# P2.net
KiCad netlist of a schematic drawn in Altium Designer
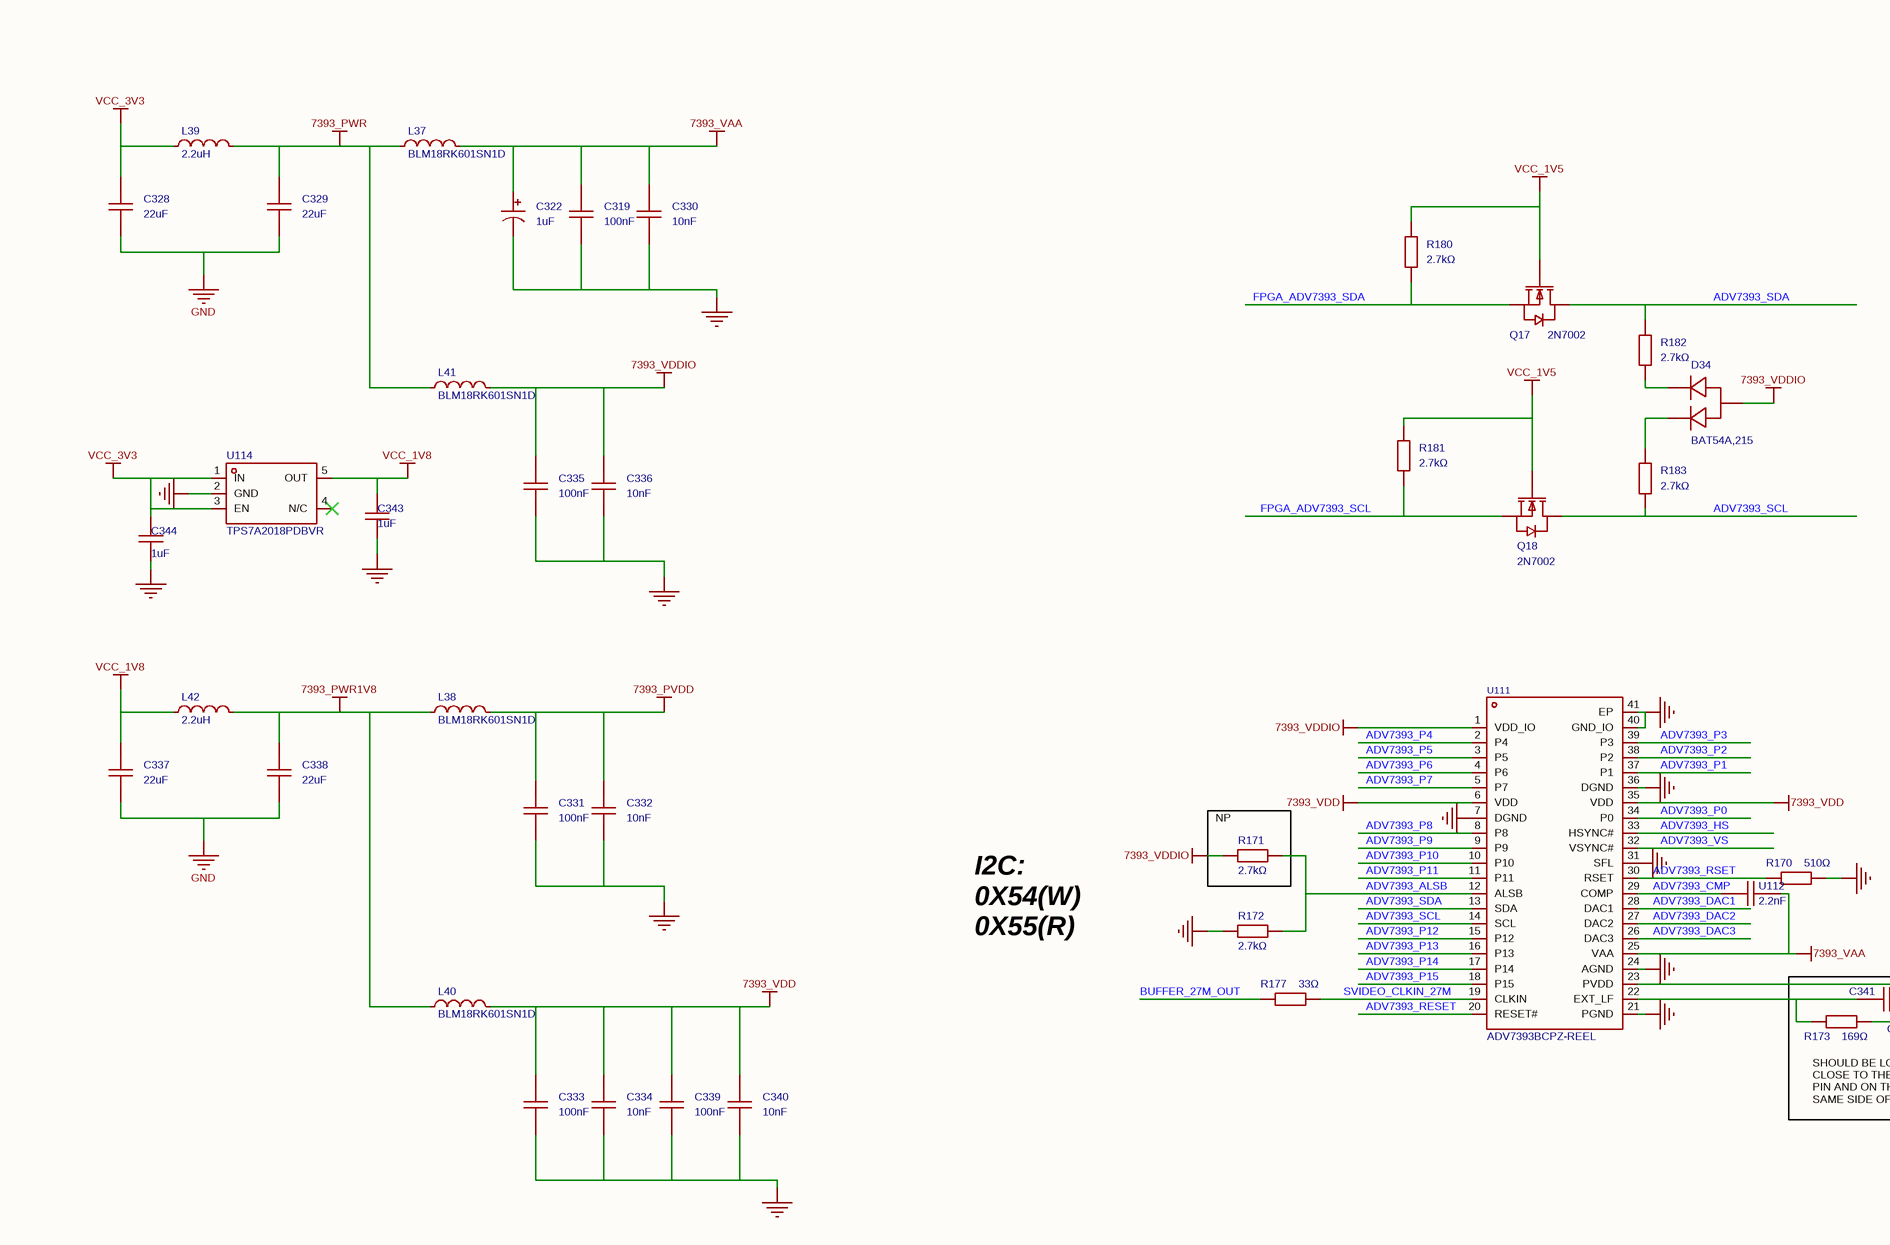
[diagram p0: P2.schdoc, top left]
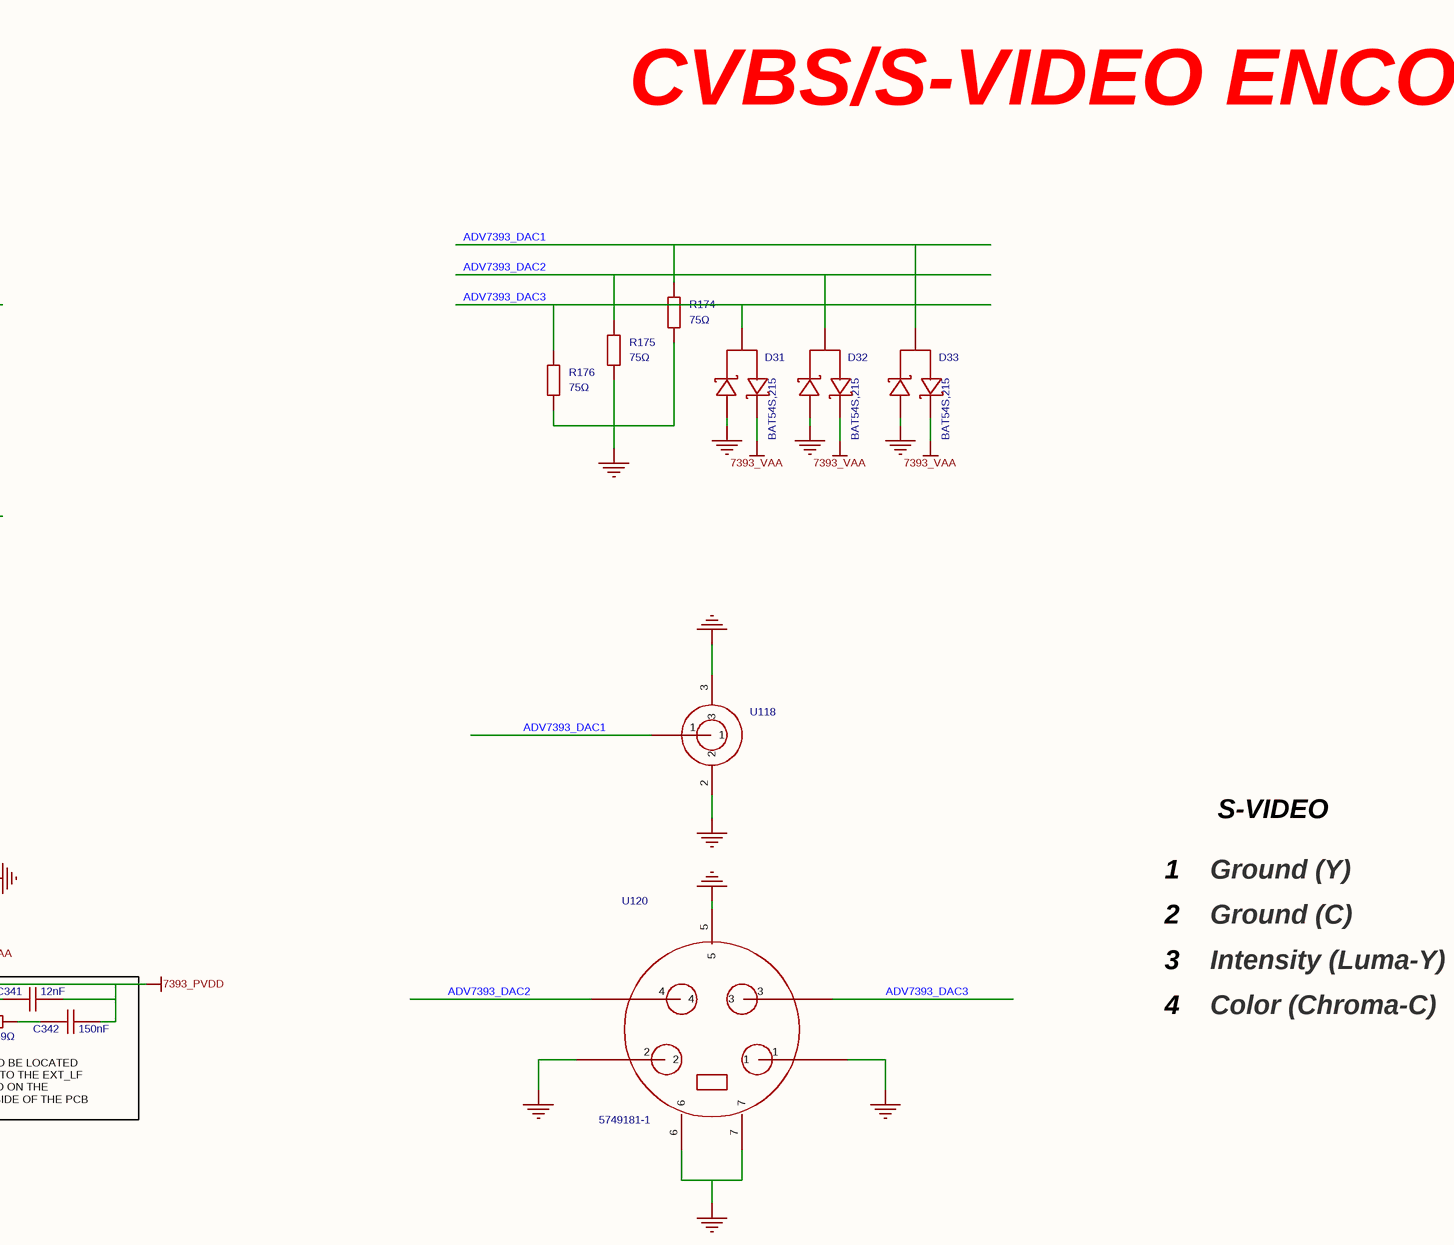
[diagram p1: P2.schdoc, top right]
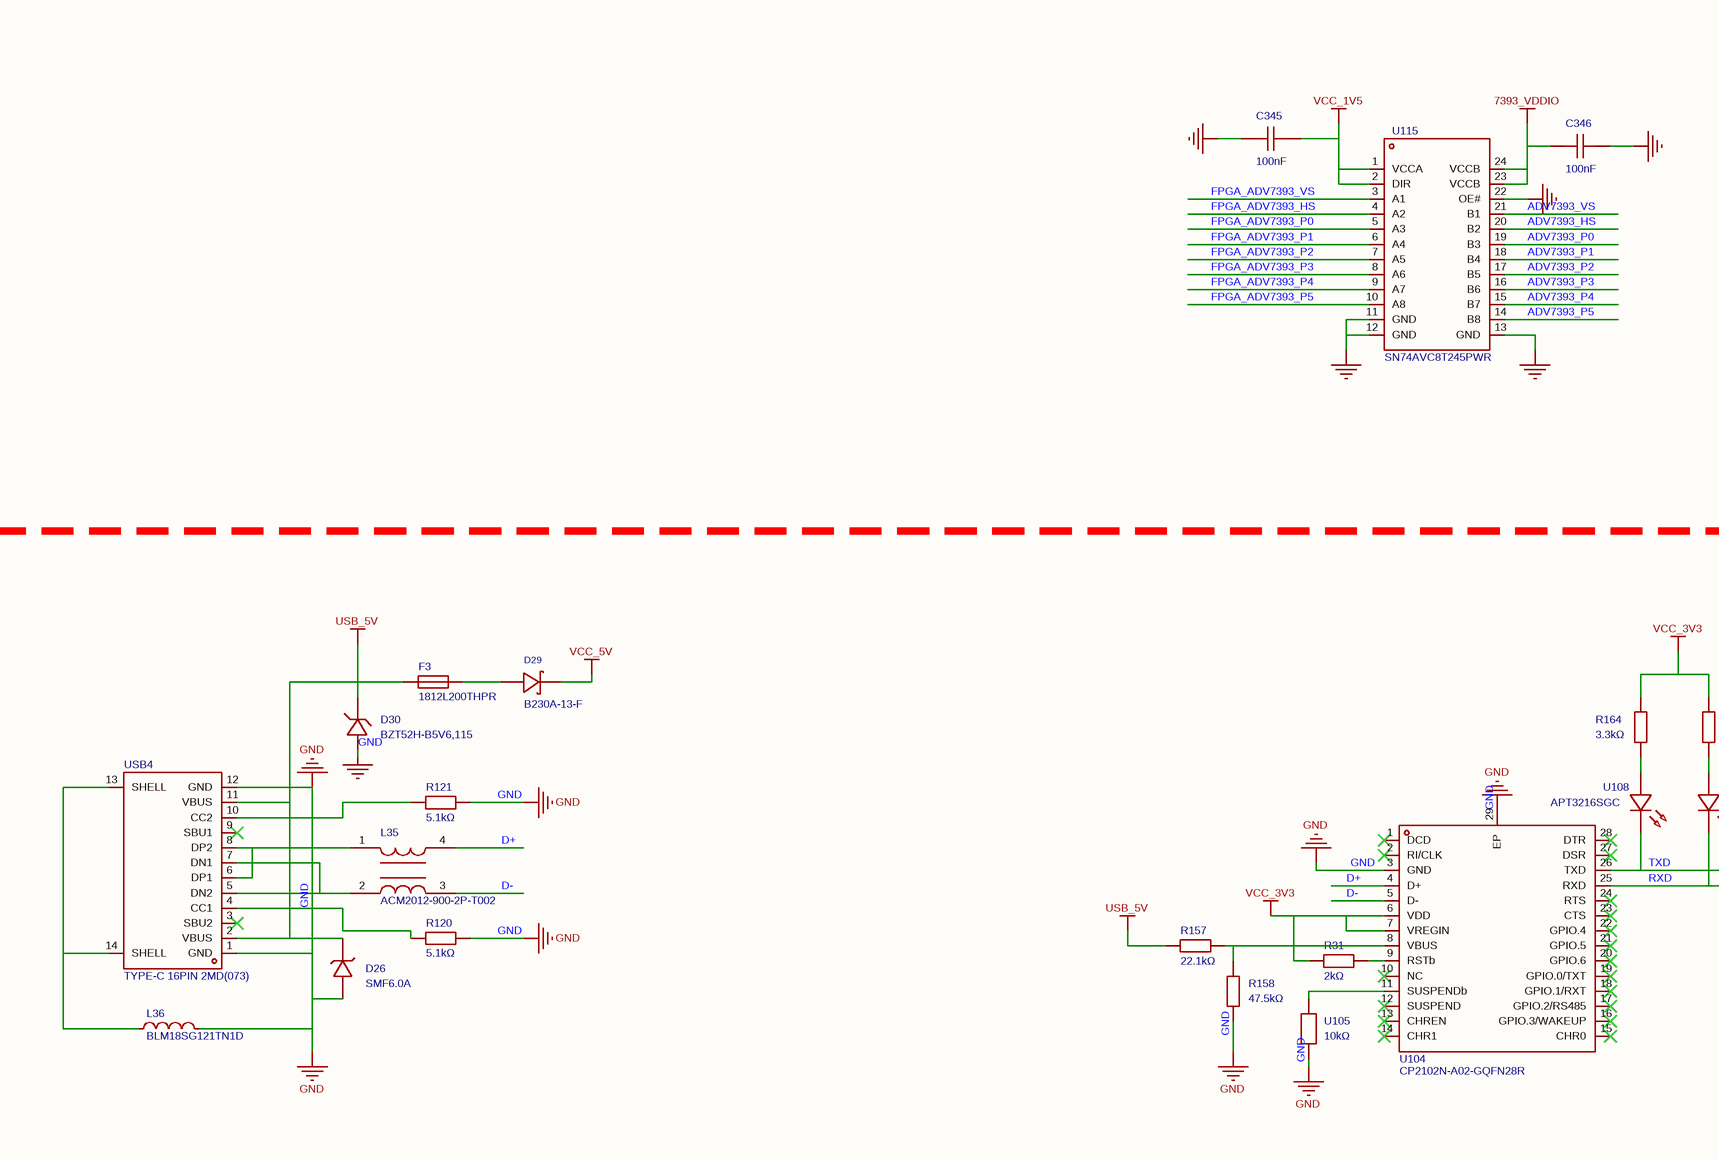
[diagram p2: P2.schdoc, bottom left]
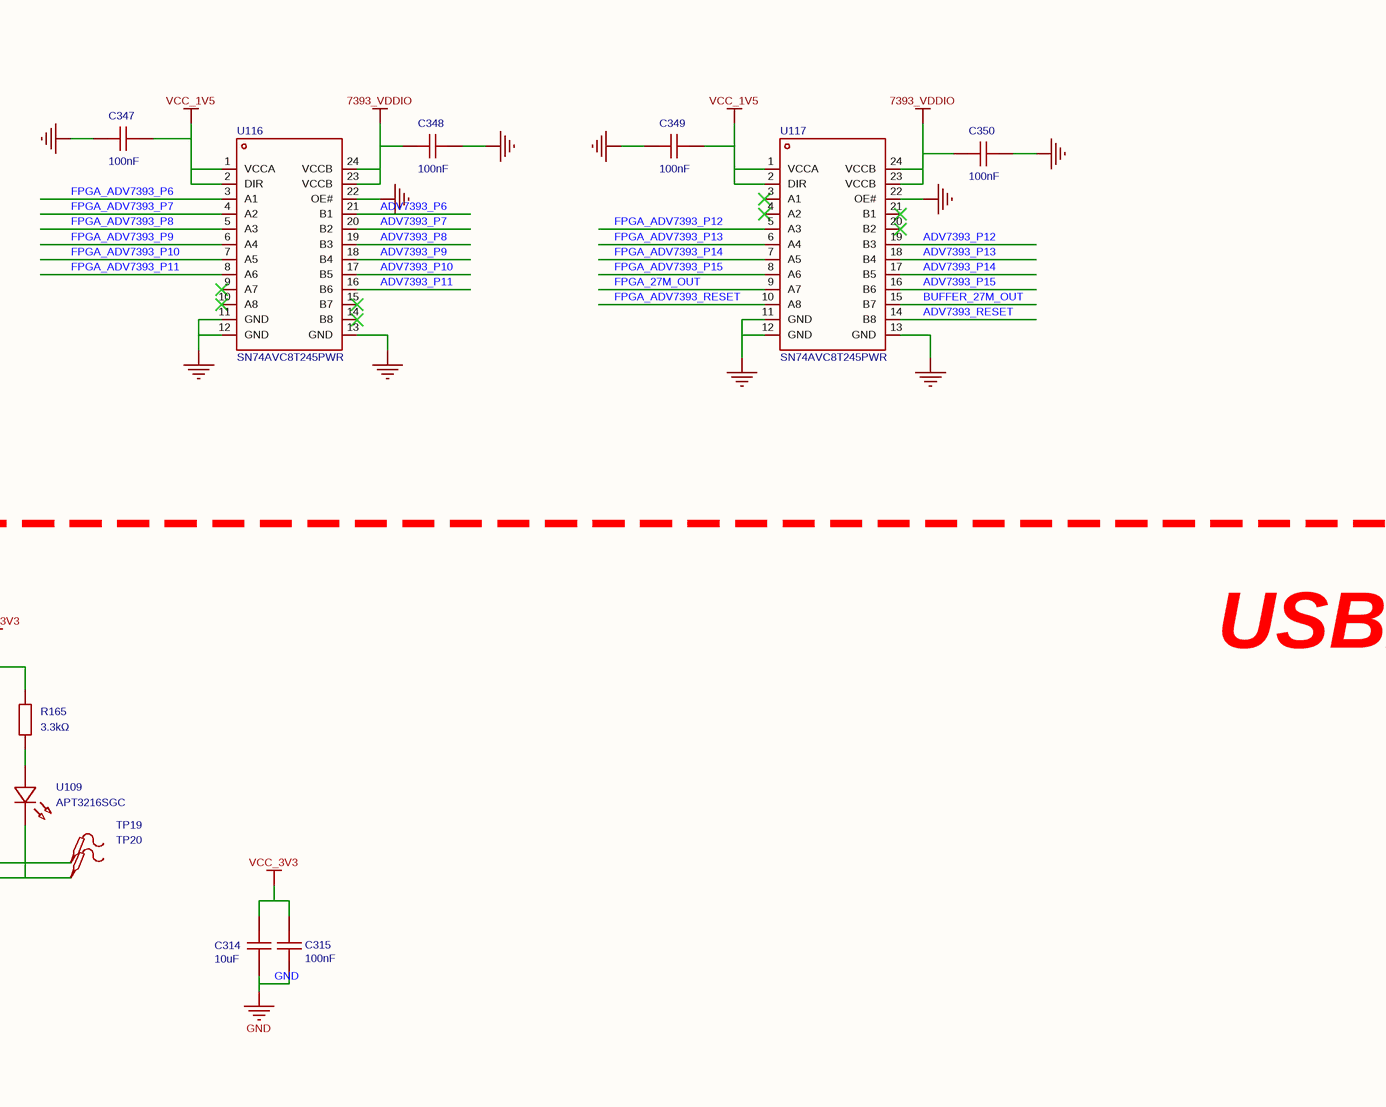
[diagram p3: P2.schdoc, bottom right]

(export (version "E")
  (design (tool "Eeschema 10.0.6"))
  (components
    (comp (ref "C314")
      (value "10uF")
      (footprint "C0603")
      (fields (field (name "MANUFACTURER") "TDK") (field (name "MANUFACTURER PART") "C1608X5R1A106M080AC"))
      (libsource (lib "altium-import") (part "root_1_10uF_"))
    )
    (comp (ref "C315")
      (value "100nF")
      (footprint "C0603")
      (description "容值:100nF;精度:±10%;额定电压:50V;材质(温度系数):X7R;")
      (fields
        (field (name "MANUFACTURER") "muRata(村田)")
        (field (name "MANUFACTURER PART") "GRM188R71H104KA93D")
      )
      (libsource (lib "altium-import") (part "root_1_GRM188R71H104KA93D_"))
    )
    (comp (ref "C319")
      (value "100nF")
      (footprint "C0402")
      (description "容值:100nF;精度:±10%;额定电压:10V;材质(温度系数):X7R;")
      (fields
        (field (name "MANUFACTURER") "muRata(村田)")
        (field (name "MANUFACTURERPART") "GCM155R71A104KA55D")
      )
      (libsource (lib "altium-import") (part "root_2_GCM155R71A104KA55D_"))
    )
    (comp (ref "C322")
      (value "1uF")
      (footprint "CAP-SMD_L3.2-W1.6-FD-1")
      (description "容值:1uF;精度:±10%;额定电压:35V;等效串联电阻:7.5Ω;")
      (fields
        (field (name "MANUFACTURER") "VISHAY(威世)")
        (field (name "MANUFACTURER PART") "293D105X9035A2TE3")
      )
      (libsource (lib "altium-import") (part "root_1_293D105X9035A2TE3_"))
    )
    (comp (ref "C328")
      (value "22uF")
      (footprint "C1210")
      (description "容值:22uF;精度:±10%;额定电压:25V;材质(温度系数):X7R;")
      (fields
        (field (name "MANUFACTURER") "muRata(村田)")
        (field (name "MANUFACTURER PART") "GRM32ER71E226KE15L")
      )
      (libsource (lib "altium-import") (part "root_1_GRM32ER71E226KE15L_"))
    )
    (comp (ref "C329")
      (value "22uF")
      (footprint "C1210")
      (description "容值:22uF;精度:±10%;额定电压:25V;材质(温度系数):X7R;")
      (fields
        (field (name "MANUFACTURER") "muRata(村田)")
        (field (name "MANUFACTURER PART") "GRM32ER71E226KE15L")
      )
      (libsource (lib "altium-import") (part "root_1_GRM32ER71E226KE15L_"))
    )
    (comp (ref "C330")
      (value "10nF")
      (footprint "C0402")
      (description "容值:10nF;精度:±10%;额定电压:50V;材质(温度系数):X7R;")
      (fields
        (field (name "MANUFACTURER") "muRata(村田)")
        (field (name "MANUFACTURER PART") "GRM155R71H103KA88D")
      )
      (libsource (lib "altium-import") (part "root_1_GRM155R71H103KA88D_"))
    )
    (comp (ref "C331")
      (value "100nF")
      (footprint "C0402")
      (description "容值:100nF;精度:±10%;额定电压:10V;材质(温度系数):X7R;")
      (fields
        (field (name "MANUFACTURER") "muRata(村田)")
        (field (name "MANUFACTURERPART") "GCM155R71A104KA55D")
      )
      (libsource (lib "altium-import") (part "root_2_GCM155R71A104KA55D_"))
    )
    (comp (ref "C332")
      (value "10nF")
      (footprint "C0402")
      (description "容值:10nF;精度:±10%;额定电压:50V;材质(温度系数):X7R;")
      (fields
        (field (name "MANUFACTURER") "muRata(村田)")
        (field (name "MANUFACTURER PART") "GRM155R71H103KA88D")
      )
      (libsource (lib "altium-import") (part "root_1_GRM155R71H103KA88D_"))
    )
    (comp (ref "C333")
      (value "100nF")
      (footprint "C0402")
      (description "容值:100nF;精度:±10%;额定电压:10V;材质(温度系数):X7R;")
      (fields
        (field (name "MANUFACTURER") "muRata(村田)")
        (field (name "MANUFACTURERPART") "GCM155R71A104KA55D")
      )
      (libsource (lib "altium-import") (part "root_2_GCM155R71A104KA55D_"))
    )
    (comp (ref "C334")
      (value "10nF")
      (footprint "C0402")
      (description "容值:10nF;精度:±10%;额定电压:50V;材质(温度系数):X7R;")
      (fields
        (field (name "MANUFACTURER") "muRata(村田)")
        (field (name "MANUFACTURER PART") "GRM155R71H103KA88D")
      )
      (libsource (lib "altium-import") (part "root_1_GRM155R71H103KA88D_"))
    )
    (comp (ref "C335")
      (value "100nF")
      (footprint "C0402")
      (description "容值:100nF;精度:±10%;额定电压:10V;材质(温度系数):X7R;")
      (fields
        (field (name "MANUFACTURER") "muRata(村田)")
        (field (name "MANUFACTURERPART") "GCM155R71A104KA55D")
      )
      (libsource (lib "altium-import") (part "root_2_GCM155R71A104KA55D_"))
    )
    (comp (ref "C336")
      (value "10nF")
      (footprint "C0402")
      (description "容值:10nF;精度:±10%;额定电压:50V;材质(温度系数):X7R;")
      (fields
        (field (name "MANUFACTURER") "muRata(村田)")
        (field (name "MANUFACTURER PART") "GRM155R71H103KA88D")
      )
      (libsource (lib "altium-import") (part "root_1_GRM155R71H103KA88D_"))
    )
    (comp (ref "C337")
      (value "22uF")
      (footprint "C1210")
      (description "容值:22uF;精度:±10%;额定电压:25V;材质(温度系数):X7R;")
      (fields
        (field (name "MANUFACTURER") "muRata(村田)")
        (field (name "MANUFACTURER PART") "GRM32ER71E226KE15L")
      )
      (libsource (lib "altium-import") (part "root_1_GRM32ER71E226KE15L_"))
    )
    (comp (ref "C338")
      (value "22uF")
      (footprint "C1210")
      (description "容值:22uF;精度:±10%;额定电压:25V;材质(温度系数):X7R;")
      (fields
        (field (name "MANUFACTURER") "muRata(村田)")
        (field (name "MANUFACTURER PART") "GRM32ER71E226KE15L")
      )
      (libsource (lib "altium-import") (part "root_1_GRM32ER71E226KE15L_"))
    )
    (comp (ref "C339")
      (value "100nF")
      (footprint "C0402")
      (description "容值:100nF;精度:±10%;额定电压:10V;材质(温度系数):X7R;")
      (fields
        (field (name "MANUFACTURER") "muRata(村田)")
        (field (name "MANUFACTURERPART") "GCM155R71A104KA55D")
      )
      (libsource (lib "altium-import") (part "root_2_GCM155R71A104KA55D_"))
    )
    (comp (ref "C340")
      (value "10nF")
      (footprint "C0402")
      (description "容值:10nF;精度:±10%;额定电压:50V;材质(温度系数):X7R;")
      (fields
        (field (name "MANUFACTURER") "muRata(村田)")
        (field (name "MANUFACTURER PART") "GRM155R71H103KA88D")
      )
      (libsource (lib "altium-import") (part "root_1_GRM155R71H103KA88D_"))
    )
    (comp (ref "C341")
      (value "12nF")
      (footprint "C0402")
      (description "容值:12nF;精度:±10%;额定电压:25V;材质(温度系数):X7R;")
      (fields
        (field (name "MANUFACTURER") "YAGEO(国巨)")
        (field (name "MANUFACTURER PART") "CC0402KRX7R8BB123")
      )
      (libsource (lib "altium-import") (part "root_0_CC0402KRX7R8BB123_"))
    )
    (comp (ref "C342")
      (value "150nF")
      (footprint "C0402")
      (description "容值:150nF;精度:±10%;额定电压:16V;材质(温度系数):X7R;")
      (fields
        (field (name "MANUFACTURER") "muRata(村田)")
        (field (name "MANUFACTURER PART") "GRM155R71C154KA12D")
      )
      (libsource (lib "altium-import") (part "root_0_GRM155R71C154KA12D_"))
    )
    (comp (ref "C343")
      (value "1uF")
      (footprint "C0402")
      (description "容值:1uF;精度:±10%;额定电压:25V;材质(温度系数):X5R;")
      (fields
        (field (name "MANUFACTURER PART") "GRM155R61E105KA12D")
        (field (name "MANUFACTURER") "muRata(村田)")
      )
      (libsource (lib "altium-import") (part "root_1_GRM155R61E105KA12D_"))
    )
    (comp (ref "C344")
      (value "1uF")
      (footprint "C0402")
      (description "容值:1uF;精度:±10%;额定电压:25V;材质(温度系数):X5R;")
      (fields
        (field (name "MANUFACTURER PART") "GRM155R61E105KA12D")
        (field (name "MANUFACTURER") "muRata(村田)")
      )
      (libsource (lib "altium-import") (part "root_1_GRM155R61E105KA12D_"))
    )
    (comp (ref "C345")
      (value "100nF")
      (footprint "C0603")
      (description "容值:100nF;精度:±10%;额定电压:50V;材质(温度系数):X7R;")
      (fields
        (field (name "MANUFACTURER") "muRata(村田)")
        (field (name "MANUFACTURER PART") "GRM188R71H104KA93D")
      )
      (libsource (lib "altium-import") (part "root_2_GRM188R71H104KA93D_"))
    )
    (comp (ref "C346")
      (value "100nF")
      (footprint "C0603")
      (description "容值:100nF;精度:±10%;额定电压:50V;材质(温度系数):X7R;")
      (fields
        (field (name "MANUFACTURER") "muRata(村田)")
        (field (name "MANUFACTURER PART") "GRM188R71H104KA93D")
      )
      (libsource (lib "altium-import") (part "root_0_GRM188R71H104KA93D_"))
    )
    (comp (ref "C347")
      (value "100nF")
      (footprint "C0603")
      (description "容值:100nF;精度:±10%;额定电压:50V;材质(温度系数):X7R;")
      (fields
        (field (name "MANUFACTURER") "muRata(村田)")
        (field (name "MANUFACTURER PART") "GRM188R71H104KA93D")
      )
      (libsource (lib "altium-import") (part "root_2_GRM188R71H104KA93D_"))
    )
    (comp (ref "C348")
      (value "100nF")
      (footprint "C0603")
      (description "容值:100nF;精度:±10%;额定电压:50V;材质(温度系数):X7R;")
      (fields
        (field (name "MANUFACTURER") "muRata(村田)")
        (field (name "MANUFACTURER PART") "GRM188R71H104KA93D")
      )
      (libsource (lib "altium-import") (part "root_0_GRM188R71H104KA93D_"))
    )
    (comp (ref "C349")
      (value "100nF")
      (footprint "C0603")
      (description "容值:100nF;精度:±10%;额定电压:50V;材质(温度系数):X7R;")
      (fields
        (field (name "MANUFACTURER") "muRata(村田)")
        (field (name "MANUFACTURER PART") "GRM188R71H104KA93D")
      )
      (libsource (lib "altium-import") (part "root_2_GRM188R71H104KA93D_"))
    )
    (comp (ref "C350")
      (value "100nF")
      (footprint "C0603")
      (description "容值:100nF;精度:±10%;额定电压:50V;材质(温度系数):X7R;")
      (fields
        (field (name "MANUFACTURER") "muRata(村田)")
        (field (name "MANUFACTURER PART") "GRM188R71H104KA93D")
      )
      (libsource (lib "altium-import") (part "root_0_GRM188R71H104KA93D_"))
    )
    (comp (ref "D26")
      (value "SMF6.0A")
      (footprint "SOD-123FL_L2.8-W1.8-LS3.7-RD-1")
      (description "极性:单向;反向截止电压(Vrwm):6V;最大钳位电压:10.3V;峰值脉冲电流(Ipp)@10/1000us:19.4A;击穿电压:6.7V;")
      (fields (field (name "MANUFACTURER") "FTR(乔光电子)"))
      (libsource (lib "altium-import") (part "root_3_SMF6.0A_C708002_"))
    )
    (comp (ref "D29")
      (value "B230A-13-F")
      (footprint "SMA_L4.4-W2.6-LS5.0-RD")
      (description "正向压降(Vf):500mV@2A;直流反向耐压(Vr):30V;平均整流电流(Io):2A;")
      (fields (field (name "MANUFACTURER") "DIODES(美台)"))
      (libsource (lib "altium-import") (part "root_0_mirrored_B230A-13-F_"))
    )
    (comp (ref "D30")
      (value "BZT52H-B5V6,115")
      (footprint "SOD-123F_L2.6-W1.6-LS3.5-RD")
      (description "二极管配置:独立式;稳压值(标称值):5.6V;稳压值(范围):5.49V~5.71V;功率:375mW;精度:±2%;")
      (fields (field (name "MANUFACTURER") "Nexperia(安世)") (field (name "TOLERANCE") "±2%"))
      (libsource (lib "altium-import") (part "root_3_mirrored_BZT52H-B5V6,115_"))
    )
    (comp (ref "D31")
      (value "BAT54S,215")
      (footprint "SOT-23-3_L3.0-W1.7-P0.95-LS2.9-BR")
      (description "二极管配置:1对串联式;正向压降(Vf):800mV@100mA;直流反向耐压(Vr):30V;平均整流电流(Io):200mA;")
      (fields (field (name "MANUFACTURER") "Nexperia(安世)"))
      (libsource (lib "altium-import") (part "root_1_BAT54S,215_"))
    )
    (comp (ref "D32")
      (value "BAT54S,215")
      (footprint "SOT-23-3_L3.0-W1.7-P0.95-LS2.9-BR")
      (description "二极管配置:1对串联式;正向压降(Vf):800mV@100mA;直流反向耐压(Vr):30V;平均整流电流(Io):200mA;")
      (fields (field (name "MANUFACTURER") "Nexperia(安世)"))
      (libsource (lib "altium-import") (part "root_1_BAT54S,215_"))
    )
    (comp (ref "D33")
      (value "BAT54S,215")
      (footprint "SOT-23-3_L3.0-W1.7-P0.95-LS2.9-BR")
      (description "二极管配置:1对串联式;正向压降(Vf):800mV@100mA;直流反向耐压(Vr):30V;平均整流电流(Io):200mA;")
      (fields (field (name "MANUFACTURER") "Nexperia(安世)"))
      (libsource (lib "altium-import") (part "root_1_BAT54S,215_"))
    )
    (comp (ref "D34")
      (value "BAT54A,215")
      (footprint "SOT-23-3_L3.0-W1.7-P0.95-LS2.9-BR")
      (description "二极管配置:1对共阳极;直流反向耐压(Vr):30V;平均整流电流(Io):200mA;")
      (fields (field (name "MANUFACTURER") "Nexperia(安世)"))
      (libsource (lib "altium-import") (part "root_3_BAT54A,215_"))
    )
    (comp (ref "F3")
      (value "1812L200THPR")
      (footprint "F1812")
      (description "最大电压:8V;最大电流:100A;保持电流:2A;跳闸电流:3.5A;")
      (fields (field (name "MANUFACTURER") "Littelfuse(美国力特)"))
      (libsource (lib "altium-import") (part "root_0_mirrored_1812L200THPR_"))
    )
    (comp (ref "L35")
      (value "ACM2012-900-2P-T002")
      (footprint "IND-SMD_4P-L2.0-W1.2-TL")
      (description "线路数:2;阻抗 @ 频率:90Ω@100MHz;额定电流:400mA;直流电阻(DCR):190mΩ;直流额定电压(VDC):50V;工作温度:-25℃~+85℃;耐电压:50V;")
      (fields (field (name "MANUFACTURER") "TDK"))
      (libsource (lib "altium-import") (part "root_0_ACM2012-900-2P-T002_"))
    )
    (comp (ref "L36")
      (value "BLM18SG121TN1D")
      (footprint "L0603")
      (description "标称阻抗@测试频率:120Ω@100MHz;误差:±25%;直流电阻(RDC):25mΩ;")
      (fields (field (name "MANUFACTURER") "muRata(村田)") (field (name "TOLERANCE") "±25%"))
      (libsource (lib "altium-import") (part "root_0_BLM18SG121TN1D_"))
    )
    (comp (ref "L37")
      (value "BLM18RK601SN1D")
      (footprint "L0603")
      (description "标称阻抗@测试频率:600Ω@100MHz;误差:±25%;直流电阻(RDC):600mΩ;")
      (fields (field (name "MANUFACTURER") "muRata(村田)") (field (name "TOLERANCE") "±25%"))
      (libsource (lib "altium-import") (part "root_0_BLM18RK601SN1D_"))
    )
    (comp (ref "L38")
      (value "BLM18RK601SN1D")
      (footprint "L0603")
      (description "标称阻抗@测试频率:600Ω@100MHz;误差:±25%;直流电阻(RDC):600mΩ;")
      (fields (field (name "MANUFACTURER") "muRata(村田)") (field (name "TOLERANCE") "±25%"))
      (libsource (lib "altium-import") (part "root_0_BLM18RK601SN1D_"))
    )
    (comp (ref "L39")
      (value "2.2uH")
      (footprint "IND-SMD_L7.0-W6.6")
      (description "电感值:2.2uH;精度:±20%;额定电流:9.5A;饱和电流(Isat):10A;类型:一体成型电感;")
      (fields (field (name "MANUFACTURER") "cjiang(长江微电)") (field (name "MANUFACTURERPART") "FXL0630-2R2-M"))
      (libsource (lib "altium-import") (part "root_0_FXL0630-2R2-M_"))
    )
    (comp (ref "L40")
      (value "BLM18RK601SN1D")
      (footprint "L0603")
      (description "标称阻抗@测试频率:600Ω@100MHz;误差:±25%;直流电阻(RDC):600mΩ;")
      (fields (field (name "MANUFACTURER") "muRata(村田)") (field (name "TOLERANCE") "±25%"))
      (libsource (lib "altium-import") (part "root_0_BLM18RK601SN1D_"))
    )
    (comp (ref "L41")
      (value "BLM18RK601SN1D")
      (footprint "L0603")
      (description "标称阻抗@测试频率:600Ω@100MHz;误差:±25%;直流电阻(RDC):600mΩ;")
      (fields (field (name "MANUFACTURER") "muRata(村田)") (field (name "TOLERANCE") "±25%"))
      (libsource (lib "altium-import") (part "root_0_BLM18RK601SN1D_"))
    )
    (comp (ref "L42")
      (value "2.2uH")
      (footprint "IND-SMD_L7.0-W6.6")
      (description "电感值:2.2uH;精度:±20%;额定电流:9.5A;饱和电流(Isat):10A;类型:一体成型电感;")
      (fields (field (name "MANUFACTURER") "cjiang(长江微电)") (field (name "MANUFACTURERPART") "FXL0630-2R2-M"))
      (libsource (lib "altium-import") (part "root_0_FXL0630-2R2-M_"))
    )
    (comp (ref "Q17")
      (value "2N7002")
      (footprint "SOT-23-3_L2.9-W1.3-P1.90-LS2.4-BR")
      (fields (field (name "MANUFACTURER") "CJ(江苏长电/长晶)"))
      (libsource (lib "altium-import") (part "root_3_2N7002_C8545_"))
    )
    (comp (ref "Q18")
      (value "2N7002")
      (footprint "SOT-23-3_L2.9-W1.3-P1.90-LS2.4-BR")
      (fields (field (name "MANUFACTURER") "CJ(江苏长电/长晶)"))
      (libsource (lib "altium-import") (part "root_3_2N7002_C8545_"))
    )
    (comp (ref "R31")
      (value "2kΩ")
      (footprint "R0402")
      (description "电阻类型:厚膜电阻;阻值:2kΩ;精度:±1%;功率:62.5mW;最大工作电压:50V;温度系数:±100ppm/℃;")
      (fields (field (name "MANUFACTURER") "YAGEO(国巨)") (field (name "MANUFACTURERPART") "RC0402FR-072KL"))
      (libsource (lib "altium-import") (part "root_0_RC0402FR-072KL_"))
    )
    (comp (ref "R120")
      (value "5.1kΩ")
      (footprint "R0402")
      (description "电阻类型:厚膜电阻;阻值:5.1kΩ;精度:±1%;功率:62.5mW;最大工作电压:50V;温度系数:±100ppm/℃;")
      (fields (field (name "MANUFACTURER PART") "RC0402FR-075K1L") (field (name "MANUFACTURER") "YAGEO(国巨)"))
      (libsource (lib "altium-import") (part "root_0_RC0402FR-075K1L_"))
    )
    (comp (ref "R121")
      (value "5.1kΩ")
      (footprint "R0402")
      (description "电阻类型:厚膜电阻;阻值:5.1kΩ;精度:±1%;功率:62.5mW;最大工作电压:50V;温度系数:±100ppm/℃;")
      (fields (field (name "MANUFACTURER PART") "RC0402FR-075K1L") (field (name "MANUFACTURER") "YAGEO(国巨)"))
      (libsource (lib "altium-import") (part "root_0_RC0402FR-075K1L_"))
    )
    (comp (ref "R157")
      (value "22.1kΩ")
      (footprint "R0402")
      (description "电阻类型:厚膜电阻;阻值:22.1kΩ;精度:±1%;功率:62.5mW;最大工作电压:50V;温度系数:±100ppm/℃;")
      (fields (field (name "MANUFACTURER") "YAGEO(国巨)") (field (name "MANUFACTURERPART") "RC0402FR-0722K1L"))
      (libsource (lib "altium-import") (part "root_2_RC0402FR-0722K1L_"))
    )
    (comp (ref "R158")
      (value "47.5kΩ")
      (footprint "R0402")
      (description "电阻类型:厚膜电阻;阻值:47.5kΩ;精度:±1%;功率:62.5mW;最大工作电压:50V;温度系数:±100ppm/℃;")
      (fields (field (name "MANUFACTURER") "YAGEO(国巨)") (field (name "MANUFACTURERPART") "AF0402FR-0747K5L"))
      (libsource (lib "altium-import") (part "root_1_AF0402FR-0747K5L_"))
    )
    (comp (ref "R164")
      (value "3.3kΩ")
      (footprint "R0805")
      (description "电阻类型:厚膜电阻;阻值:3.3kΩ;精度:±1%;功率:125mW;最大工作电压:150V;温度系数:±100ppm/℃;")
      (fields (field (name "MANUFACTURER") "YAGEO(国巨)") (field (name "MANUFACTURERPART") "RC0805FR-073K3L"))
      (libsource (lib "altium-import") (part "root_1_mirrored_RC0805FR-073K3L_"))
    )
    (comp (ref "R165")
      (value "3.3kΩ")
      (footprint "R0805")
      (description "电阻类型:厚膜电阻;阻值:3.3kΩ;精度:±1%;功率:125mW;最大工作电压:150V;温度系数:±100ppm/℃;")
      (fields (field (name "MANUFACTURER") "YAGEO(国巨)") (field (name "MANUFACTURERPART") "RC0805FR-073K3L"))
      (libsource (lib "altium-import") (part "root_1_mirrored_RC0805FR-073K3L_"))
    )
    (comp (ref "R170")
      (value "510Ω")
      (footprint "R0402")
      (description "电阻类型:厚膜电阻;阻值:510Ω;精度:±1%;功率:62.5mW;最大工作电压:50V;温度系数:±100ppm/℃;")
      (fields (field (name "MANUFACTURER") "YAGEO(国巨)") (field (name "MANUFACTURERPART") "RC0402FR-07510RL"))
      (libsource (lib "altium-import") (part "root_0_RC0402FR-07510RL_"))
    )
    (comp (ref "R171")
      (value "2.7kΩ")
      (footprint "R0402")
      (description "电阻类型:厚膜电阻;阻值:2.7kΩ;精度:±1%;功率:62.5mW;最大工作电压:50V;温度系数:±100ppm/℃;")
      (fields (field (name "MANUFACTURER") "YAGEO(国巨)") (field (name "MANUFACTURERPART") "RC0402FR-072K7L"))
      (libsource (lib "altium-import") (part "root_2_RC0402FR-072K7L_"))
    )
    (comp (ref "R172")
      (value "2.7kΩ")
      (footprint "R0402")
      (description "电阻类型:厚膜电阻;阻值:2.7kΩ;精度:±1%;功率:62.5mW;最大工作电压:50V;温度系数:±100ppm/℃;")
      (fields (field (name "MANUFACTURER") "YAGEO(国巨)") (field (name "MANUFACTURERPART") "RC0402FR-072K7L"))
      (libsource (lib "altium-import") (part "root_2_RC0402FR-072K7L_"))
    )
    (comp (ref "R173")
      (value "169Ω")
      (footprint "R0402")
      (description "电阻类型:厚膜电阻;阻值:169Ω;精度:±1%;功率:62.5mW;最大工作电压:50V;温度系数:±100ppm/℃;")
      (fields (field (name "MANUFACTURER") "YAGEO(国巨)") (field (name "MANUFACTURERPART") "RC0402FR-07169RL"))
      (libsource (lib "altium-import") (part "root_0_RC0402FR-07169RL_"))
    )
    (comp (ref "R174")
      (value "75Ω")
      (footprint "R0805")
      (description "电阻类型:厚膜电阻;阻值:75Ω;精度:±1%;功率:125mW;最大工作电压:150V;温度系数:±100ppm/℃;")
      (fields (field (name "MANUFACTURER") "YAGEO(国巨)") (field (name "MANUFACTURERPART") "RC0805FR-0775RL"))
      (libsource (lib "altium-import") (part "root_3_RC0805FR-0775RL_"))
    )
    (comp (ref "R175")
      (value "75Ω")
      (footprint "R0805")
      (description "电阻类型:厚膜电阻;阻值:75Ω;精度:±1%;功率:125mW;最大工作电压:150V;温度系数:±100ppm/℃;")
      (fields (field (name "MANUFACTURER") "YAGEO(国巨)") (field (name "MANUFACTURERPART") "RC0805FR-0775RL"))
      (libsource (lib "altium-import") (part "root_1_mirrored_RC0805FR-0775RL_"))
    )
    (comp (ref "R176")
      (value "75Ω")
      (footprint "R0805")
      (description "电阻类型:厚膜电阻;阻值:75Ω;精度:±1%;功率:125mW;最大工作电压:150V;温度系数:±100ppm/℃;")
      (fields (field (name "MANUFACTURER") "YAGEO(国巨)") (field (name "MANUFACTURERPART") "RC0805FR-0775RL"))
      (libsource (lib "altium-import") (part "root_1_mirrored_RC0805FR-0775RL_"))
    )
    (comp (ref "R177")
      (value "33Ω")
      (footprint "R0402")
      (description "电阻类型:厚膜电阻;阻值:33Ω;精度:±1%;功率:62.5mW;最大工作电压:50V;温度系数:±100ppm/℃;")
      (fields (field (name "MANUFACTURER") "YAGEO(国巨)") (field (name "MANUFACTURERPART") "RC0402FR-0733RL"))
      (libsource (lib "altium-import") (part "root_0_RC0402FR-0733RL_"))
    )
    (comp (ref "R180")
      (value "2.7kΩ")
      (footprint "R0402")
      (description "电阻类型:厚膜电阻;阻值:2.7kΩ;精度:±1%;功率:62.5mW;最大工作电压:50V;温度系数:±100ppm/℃;")
      (fields (field (name "MANUFACTURER") "YAGEO(国巨)") (field (name "MANUFACTURERPART") "RC0402FR-072K7L"))
      (libsource (lib "altium-import") (part "root_1_RC0402FR-072K7L_"))
    )
    (comp (ref "R181")
      (value "2.7kΩ")
      (footprint "R0402")
      (description "电阻类型:厚膜电阻;阻值:2.7kΩ;精度:±1%;功率:62.5mW;最大工作电压:50V;温度系数:±100ppm/℃;")
      (fields (field (name "MANUFACTURER") "YAGEO(国巨)") (field (name "MANUFACTURERPART") "RC0402FR-072K7L"))
      (libsource (lib "altium-import") (part "root_1_RC0402FR-072K7L_"))
    )
    (comp (ref "R182")
      (value "2.7kΩ")
      (footprint "R0402")
      (description "电阻类型:厚膜电阻;阻值:2.7kΩ;精度:±1%;功率:62.5mW;最大工作电压:50V;温度系数:±100ppm/℃;")
      (fields (field (name "MANUFACTURER") "YAGEO(国巨)") (field (name "MANUFACTURERPART") "RC0402FR-072K7L"))
      (libsource (lib "altium-import") (part "root_1_RC0402FR-072K7L_"))
    )
    (comp (ref "R183")
      (value "2.7kΩ")
      (footprint "R0402")
      (description "电阻类型:厚膜电阻;阻值:2.7kΩ;精度:±1%;功率:62.5mW;最大工作电压:50V;温度系数:±100ppm/℃;")
      (fields (field (name "MANUFACTURER") "YAGEO(国巨)") (field (name "MANUFACTURERPART") "RC0402FR-072K7L"))
      (libsource (lib "altium-import") (part "root_1_RC0402FR-072K7L_"))
    )
    (comp (ref "TP19")
      (value "~")
      (footprint "Test-Point-0.5mm")
      (description "Test Point 测试点")
      (libsource (lib "altium-import") (part "root_0_Test-Point_"))
    )
    (comp (ref "TP20")
      (value "~")
      (footprint "Test-Point-0.5mm")
      (description "Test Point 测试点")
      (libsource (lib "altium-import") (part "root_0_Test-Point_"))
    )
    (comp (ref "U104")
      (value "CP2102N-A02-GQFN28R")
      (footprint "QFN-28_L5.0-W5.0-P0.50-TL-EP3.3")
      (description "应用功能:USB转UART;接口协议:UART;")
      (fields (field (name "MANUFACTURER") "SKYWORKS/SILICON LABS(芯科)"))
      (libsource (lib "altium-import") (part "root_0_CP2102N-A02-GQFN28R_"))
    )
    (comp (ref "U105")
      (value "10kΩ")
      (footprint "R0402")
      (description "电阻类型:厚膜电阻;阻值:10kΩ;精度:±1%;功率:62.5mW;最大工作电压:50V;温度系数:±100ppm/℃;")
      (fields (field (name "MANUFACTURER") "YAGEO(国巨)") (field (name "MANUFACTURER PART") "RC0402FR-0710KL"))
      (libsource (lib "altium-import") (part "root_3_RC0402FR-0710KL_"))
    )
    (comp (ref "U108")
      (value "APT3216SGC")
      (footprint "LED1206-RD")
      (description "发光颜色:翠绿色;正向电压(VF):2.2V;正向电流:20mA;主波长:568nm;透镜颜色:无色透明透镜;发光强度:12mcd;发光角度:120°;")
      (fields (field (name "MANUFACTURER") "Kingbright"))
      (libsource (lib "altium-import") (part "root_1_mirrored_APT3216SGC_"))
    )
    (comp (ref "U109")
      (value "APT3216SGC")
      (footprint "LED1206-RD")
      (description "发光颜色:翠绿色;正向电压(VF):2.2V;正向电流:20mA;主波长:568nm;透镜颜色:无色透明透镜;发光强度:12mcd;发光角度:120°;")
      (fields (field (name "MANUFACTURER") "Kingbright"))
      (libsource (lib "altium-import") (part "root_1_mirrored_APT3216SGC_"))
    )
    (comp (ref "U111")
      (value "ADV7393BCPZ-REEL")
      (footprint "LFCSP-40_L6.0-W6.0-P0.50-BL-EP4.1")
      (description "类型:视频编码器;")
      (fields (field (name "MANUFACTURER") "ADI(亚德诺)"))
      (libsource (lib "altium-import") (part "root_0_ADV7393BCPZ-REEL_"))
    )
    (comp (ref "U112")
      (value "2.2nF")
      (footprint "C0402")
      (description "容值:2.2nF;精度:±2%;额定电压:50V;材质(温度系数):C0G;")
      (fields
        (field (name "MANUFACTURER") "muRata(村田)")
        (field (name "MANUFACTURERPART") "GRM1555C1H222GA01D")
      )
      (libsource (lib "altium-import") (part "root_0_GRM1555C1H222GA01D_"))
    )
    (comp (ref "U114")
      (value "TPS7A2018PDBVR")
      (footprint "SOT-23-5_L2.9-W1.6-P0.95-LS2.8-BR")
      (description "输出类型:固定;最大输入电压:6V;输出电压:1.8V;最大输出电流:300mA;输出极性:正极;")
      (fields (field (name "MANUFACTURER") "TI(德州仪器)"))
      (libsource (lib "altium-import") (part "root_0_TPS7A2018PDBVR_"))
    )
    (comp (ref "U115")
      (value "SN74AVC8T245PWR")
      (footprint "TSSOP-24_L7.8-W4.4-P0.65-LS6.4-BL")
      (description "电路数:1;每个电路通道数:8;")
      (fields (field (name "MANUFACTURER") "TI(德州仪器)"))
      (libsource (lib "altium-import") (part "root_0_SN74AVC8T245PWR_"))
    )
    (comp (ref "U116")
      (value "SN74AVC8T245PWR")
      (footprint "TSSOP-24_L7.8-W4.4-P0.65-LS6.4-BL")
      (description "电路数:1;每个电路通道数:8;")
      (fields (field (name "MANUFACTURER") "TI(德州仪器)"))
      (libsource (lib "altium-import") (part "root_0_SN74AVC8T245PWR_"))
    )
    (comp (ref "U117")
      (value "SN74AVC8T245PWR")
      (footprint "TSSOP-24_L7.8-W4.4-P0.65-LS6.4-BL")
      (description "电路数:1;每个电路通道数:8;")
      (fields (field (name "MANUFACTURER") "TI(德州仪器)"))
      (libsource (lib "altium-import") (part "root_0_SN74AVC8T245PWR_"))
    )
    (comp (ref "U118")
      (value "~")
      (footprint "RCA-Y")
      (description "黄色RCA端子")
      (libsource (lib "altium-import") (part "root_2_RCA-Y_"))
    )
    (comp (ref "U120")
      (value "~")
      (footprint "MINI_DIN_4")
      (description "MINI_DIN_4PIN，S-VIDEO用")
      (fields (field (name "MANUFACTURER PART") "5749181-1"))
      (libsource (lib "altium-import") (part "root_0_MINI_DIN_4_"))
    )
    (comp (ref "USB4")
      (value "TYPE-C 16PIN 2MD(073)")
      (footprint "USB-C-SMD_TYPE-C-6PIN-2MD-073")
      (description "连接器类型:Type-C;标准:-;公母:母;触点数量:16P;端口数量:1;安装方式:卧贴;额定电流 - 电源:5A;工作温度范围:-25℃~+85℃;")
      (fields (field (name "MANUFACTURER") "SHOU HAN(首韩)"))
      (libsource (lib "altium-import") (part "root_2_TYPE-C 16PIN 2MD(073)_"))
    )
  )
  (nets
    (net (code "1") (name "/ADV7393_ALSB") (class "Default")
      (node (ref "R171") (pin "1") (pinfunction "1_1") (pintype "passive"))
      (node (ref "R172") (pin "1") (pinfunction "1_1") (pintype "passive"))
      (node (ref "U111") (pin "12") (pinfunction "ALSB_12") (pintype "passive"))
    )
    (net (code "2") (name "/ADV7393_CMP") (class "Default")
      (node (ref "U111") (pin "29") (pinfunction "COMP_29") (pintype "passive"))
      (node (ref "U112") (pin "1") (pinfunction "1_1") (pintype "passive"))
    )
    (net (code "3") (name "/ADV7393_DAC1") (class "Default")
      (node (ref "D33") (pin "3") (pinfunction "AK_3") (pintype "passive"))
      (node (ref "R174") (pin "1") (pinfunction "1_1") (pintype "passive"))
      (node (ref "U111") (pin "28") (pinfunction "DAC1_28") (pintype "passive"))
      (node (ref "U118") (pin "1") (pinfunction "1_1") (pintype "passive"))
    )
    (net (code "4") (name "/ADV7393_DAC2") (class "Default")
      (node (ref "D32") (pin "3") (pinfunction "AK_3") (pintype "passive"))
      (node (ref "R175") (pin "2") (pinfunction "2_2") (pintype "passive"))
      (node (ref "U111") (pin "27") (pinfunction "DAC2_27") (pintype "passive"))
      (node (ref "U120") (pin "4") (pinfunction "4_4") (pintype "passive"))
    )
    (net (code "5") (name "/ADV7393_DAC3") (class "Default")
      (node (ref "D31") (pin "3") (pinfunction "AK_3") (pintype "passive"))
      (node (ref "R176") (pin "2") (pinfunction "2_2") (pintype "passive"))
      (node (ref "U111") (pin "26") (pinfunction "DAC3_26") (pintype "passive"))
      (node (ref "U120") (pin "3") (pinfunction "3_3") (pintype "passive"))
    )
    (net (code "6") (name "/ADV7393_HS") (class "Default")
      (node (ref "U111") (pin "33") (pinfunction "HSYNC#_33") (pintype "passive"))
      (node (ref "U115") (pin "20") (pinfunction "B2_20") (pintype "passive"))
    )
    (net (code "7") (name "/ADV7393_P0") (class "Default")
      (node (ref "U111") (pin "34") (pinfunction "P0_34") (pintype "passive"))
      (node (ref "U115") (pin "19") (pinfunction "B3_19") (pintype "passive"))
    )
    (net (code "8") (name "/ADV7393_P1") (class "Default")
      (node (ref "U111") (pin "37") (pinfunction "P1_37") (pintype "passive"))
      (node (ref "U115") (pin "18") (pinfunction "B4_18") (pintype "passive"))
    )
    (net (code "9") (name "/ADV7393_P2") (class "Default")
      (node (ref "U111") (pin "38") (pinfunction "P2_38") (pintype "passive"))
      (node (ref "U115") (pin "17") (pinfunction "B5_17") (pintype "passive"))
    )
    (net (code "10") (name "/ADV7393_P3") (class "Default")
      (node (ref "U111") (pin "39") (pinfunction "P3_39") (pintype "passive"))
      (node (ref "U115") (pin "16") (pinfunction "B6_16") (pintype "passive"))
    )
    (net (code "11") (name "/ADV7393_P4") (class "Default")
      (node (ref "U111") (pin "2") (pinfunction "P4_2") (pintype "passive"))
      (node (ref "U115") (pin "15") (pinfunction "B7_15") (pintype "passive"))
    )
    (net (code "12") (name "/ADV7393_P5") (class "Default")
      (node (ref "U111") (pin "3") (pinfunction "P5_3") (pintype "passive"))
      (node (ref "U115") (pin "14") (pinfunction "B8_14") (pintype "passive"))
    )
    (net (code "13") (name "/ADV7393_P6") (class "Default")
      (node (ref "U111") (pin "4") (pinfunction "P6_4") (pintype "passive"))
      (node (ref "U116") (pin "21") (pinfunction "B1_21") (pintype "passive"))
    )
    (net (code "14") (name "/ADV7393_P7") (class "Default")
      (node (ref "U111") (pin "5") (pinfunction "P7_5") (pintype "passive"))
      (node (ref "U116") (pin "20") (pinfunction "B2_20") (pintype "passive"))
    )
    (net (code "15") (name "/ADV7393_P8") (class "Default")
      (node (ref "U111") (pin "8") (pinfunction "P8_8") (pintype "passive"))
      (node (ref "U116") (pin "19") (pinfunction "B3_19") (pintype "passive"))
    )
    (net (code "16") (name "/ADV7393_P9") (class "Default")
      (node (ref "U111") (pin "9") (pinfunction "P9_9") (pintype "passive"))
      (node (ref "U116") (pin "18") (pinfunction "B4_18") (pintype "passive"))
    )
    (net (code "17") (name "/ADV7393_P10") (class "Default")
      (node (ref "U111") (pin "10") (pinfunction "P10_10") (pintype "passive"))
      (node (ref "U116") (pin "17") (pinfunction "B5_17") (pintype "passive"))
    )
    (net (code "18") (name "/ADV7393_P11") (class "Default")
      (node (ref "U111") (pin "11") (pinfunction "P11_11") (pintype "passive"))
      (node (ref "U116") (pin "16") (pinfunction "B6_16") (pintype "passive"))
    )
    (net (code "19") (name "/ADV7393_P12") (class "Default")
      (node (ref "U111") (pin "15") (pinfunction "P12_15") (pintype "passive"))
      (node (ref "U117") (pin "19") (pinfunction "B3_19") (pintype "passive"))
    )
    (net (code "20") (name "/ADV7393_P13") (class "Default")
      (node (ref "U111") (pin "16") (pinfunction "P13_16") (pintype "passive"))
      (node (ref "U117") (pin "18") (pinfunction "B4_18") (pintype "passive"))
    )
    (net (code "21") (name "/ADV7393_P14") (class "Default")
      (node (ref "U111") (pin "17") (pinfunction "P14_17") (pintype "passive"))
      (node (ref "U117") (pin "17") (pinfunction "B5_17") (pintype "passive"))
    )
    (net (code "22") (name "/ADV7393_P15") (class "Default")
      (node (ref "U111") (pin "18") (pinfunction "P15_18") (pintype "passive"))
      (node (ref "U117") (pin "16") (pinfunction "B6_16") (pintype "passive"))
    )
    (net (code "23") (name "/ADV7393_RESET") (class "Default")
      (node (ref "U111") (pin "20") (pinfunction "RESET#_20") (pintype "passive"))
      (node (ref "U117") (pin "14") (pinfunction "B8_14") (pintype "passive"))
    )
    (net (code "24") (name "/ADV7393_RSET") (class "Default")
      (node (ref "R170") (pin "1") (pinfunction "1_1") (pintype "passive"))
      (node (ref "U111") (pin "30") (pinfunction "RSET_30") (pintype "passive"))
    )
    (net (code "25") (name "/ADV7393_SCL") (class "Default")
      (node (ref "Q18") (pin "3") (pinfunction "D_3") (pintype "passive"))
      (node (ref "R183") (pin "1") (pinfunction "1_1") (pintype "passive"))
      (node (ref "U111") (pin "14") (pinfunction "SCL_14") (pintype "passive"))
    )
    (net (code "26") (name "/ADV7393_SDA") (class "Default")
      (node (ref "Q17") (pin "3") (pinfunction "D_3") (pintype "passive"))
      (node (ref "R182") (pin "2") (pinfunction "2_2") (pintype "passive"))
      (node (ref "U111") (pin "13") (pinfunction "SDA_13") (pintype "passive"))
    )
    (net (code "27") (name "/ADV7393_VS") (class "Default")
      (node (ref "U111") (pin "32") (pinfunction "VSYNC#_32") (pintype "passive"))
      (node (ref "U115") (pin "21") (pinfunction "B1_21") (pintype "passive"))
    )
    (net (code "28") (name "/BUFFER_27M_OUT") (class "Default")
      (node (ref "R177") (pin "1") (pinfunction "1_1") (pintype "passive"))
      (node (ref "U117") (pin "15") (pinfunction "B7_15") (pintype "passive"))
    )
    (net (code "29") (name "/D+") (class "Default")
      (node (ref "L35") (pin "4") (pinfunction "4_4") (pintype "passive"))
      (node (ref "U104") (pin "4") (pinfunction "D+_4") (pintype "passive"))
    )
    (net (code "30") (name "/D-") (class "Default")
      (node (ref "L35") (pin "3") (pinfunction "3_3") (pintype "passive"))
      (node (ref "U104") (pin "5") (pinfunction "D-_5") (pintype "passive"))
    )
    (net (code "31") (name "/FPGA_27M_OUT") (class "Default")
      (node (ref "U117") (pin "9") (pinfunction "A7_9") (pintype "passive"))
    )
    (net (code "32") (name "/FPGA_ADV7393_HS") (class "Default")
      (node (ref "U115") (pin "4") (pinfunction "A2_4") (pintype "passive"))
    )
    (net (code "33") (name "/FPGA_ADV7393_P0") (class "Default")
      (node (ref "U115") (pin "5") (pinfunction "A3_5") (pintype "passive"))
    )
    (net (code "34") (name "/FPGA_ADV7393_P1") (class "Default")
      (node (ref "U115") (pin "6") (pinfunction "A4_6") (pintype "passive"))
    )
    (net (code "35") (name "/FPGA_ADV7393_P2") (class "Default")
      (node (ref "U115") (pin "7") (pinfunction "A5_7") (pintype "passive"))
    )
    (net (code "36") (name "/FPGA_ADV7393_P3") (class "Default")
      (node (ref "U115") (pin "8") (pinfunction "A6_8") (pintype "passive"))
    )
    (net (code "37") (name "/FPGA_ADV7393_P4") (class "Default")
      (node (ref "U115") (pin "9") (pinfunction "A7_9") (pintype "passive"))
    )
    (net (code "38") (name "/FPGA_ADV7393_P5") (class "Default")
      (node (ref "U115") (pin "10") (pinfunction "A8_10") (pintype "passive"))
    )
    (net (code "39") (name "/FPGA_ADV7393_P6") (class "Default")
      (node (ref "U116") (pin "3") (pinfunction "A1_3") (pintype "passive"))
    )
    (net (code "40") (name "/FPGA_ADV7393_P7") (class "Default")
      (node (ref "U116") (pin "4") (pinfunction "A2_4") (pintype "passive"))
    )
    (net (code "41") (name "/FPGA_ADV7393_P8") (class "Default")
      (node (ref "U116") (pin "5") (pinfunction "A3_5") (pintype "passive"))
    )
    (net (code "42") (name "/FPGA_ADV7393_P9") (class "Default")
      (node (ref "U116") (pin "6") (pinfunction "A4_6") (pintype "passive"))
    )
    (net (code "43") (name "/FPGA_ADV7393_P10") (class "Default")
      (node (ref "U116") (pin "7") (pinfunction "A5_7") (pintype "passive"))
    )
    (net (code "44") (name "/FPGA_ADV7393_P11") (class "Default")
      (node (ref "U116") (pin "8") (pinfunction "A6_8") (pintype "passive"))
    )
    (net (code "45") (name "/FPGA_ADV7393_P12") (class "Default")
      (node (ref "U117") (pin "5") (pinfunction "A3_5") (pintype "passive"))
    )
    (net (code "46") (name "/FPGA_ADV7393_P13") (class "Default")
      (node (ref "U117") (pin "6") (pinfunction "A4_6") (pintype "passive"))
    )
    (net (code "47") (name "/FPGA_ADV7393_P14") (class "Default")
      (node (ref "U117") (pin "7") (pinfunction "A5_7") (pintype "passive"))
    )
    (net (code "48") (name "/FPGA_ADV7393_P15") (class "Default")
      (node (ref "U117") (pin "8") (pinfunction "A6_8") (pintype "passive"))
    )
    (net (code "49") (name "/FPGA_ADV7393_RESET") (class "Default")
      (node (ref "U117") (pin "10") (pinfunction "A8_10") (pintype "passive"))
    )
    (net (code "50") (name "/FPGA_ADV7393_SCL") (class "Default")
      (node (ref "Q18") (pin "2") (pinfunction "S_2") (pintype "passive"))
      (node (ref "R181") (pin "1") (pinfunction "1_1") (pintype "passive"))
    )
    (net (code "51") (name "/FPGA_ADV7393_SDA") (class "Default")
      (node (ref "Q17") (pin "2") (pinfunction "S_2") (pintype "passive"))
      (node (ref "R180") (pin "1") (pinfunction "1_1") (pintype "passive"))
    )
    (net (code "52") (name "/FPGA_ADV7393_VS") (class "Default")
      (node (ref "U115") (pin "3") (pinfunction "A1_3") (pintype "passive"))
    )
    (net (code "53") (name "/RXD") (class "Default")
      (node (ref "TP20") (pin "1") (pinfunction "1_1") (pintype "passive"))
      (node (ref "U104") (pin "25") (pinfunction "RXD_25") (pintype "passive"))
      (node (ref "U109") (pin "1") (pinfunction "K_1") (pintype "passive"))
    )
    (net (code "54") (name "/SVIDEO_CLKIN_27M") (class "Default")
      (node (ref "R177") (pin "2") (pinfunction "2_2") (pintype "passive"))
      (node (ref "U111") (pin "19") (pinfunction "CLKIN_19") (pintype "passive"))
    )
    (net (code "55") (name "/TXD") (class "Default")
      (node (ref "TP19") (pin "1") (pinfunction "1_1") (pintype "passive"))
      (node (ref "U104") (pin "26") (pinfunction "TXD_26") (pintype "passive"))
      (node (ref "U108") (pin "1") (pinfunction "K_1") (pintype "passive"))
    )
    (net (code "56") (name "7393_PVDD") (class "Default")
      (node (ref "C331") (pin "1") (pinfunction "1_1") (pintype "passive"))
      (node (ref "C332") (pin "2") (pinfunction "2_2") (pintype "passive"))
      (node (ref "C341") (pin "2") (pinfunction "2_2") (pintype "passive"))
      (node (ref "C342") (pin "2") (pinfunction "2_2") (pintype "passive"))
      (node (ref "L38") (pin "2") (pinfunction "2_2") (pintype "passive"))
      (node (ref "U111") (pin "23") (pinfunction "PVDD_23") (pintype "passive"))
    )
    (net (code "57") (name "7393_PWR") (class "Default")
      (node (ref "C329") (pin "2") (pinfunction "2_2") (pintype "passive"))
      (node (ref "L37") (pin "1") (pinfunction "1_1") (pintype "passive"))
      (node (ref "L39") (pin "2") (pinfunction "2_2") (pintype "passive"))
      (node (ref "L41") (pin "1") (pinfunction "1_1") (pintype "passive"))
    )
    (net (code "58") (name "7393_PWR1V8") (class "Default")
      (node (ref "C338") (pin "2") (pinfunction "2_2") (pintype "passive"))
      (node (ref "L38") (pin "1") (pinfunction "1_1") (pintype "passive"))
      (node (ref "L40") (pin "1") (pinfunction "1_1") (pintype "passive"))
      (node (ref "L42") (pin "2") (pinfunction "2_2") (pintype "passive"))
    )
    (net (code "59") (name "7393_VAA") (class "Default")
      (node (ref "C319") (pin "1") (pinfunction "1_1") (pintype "passive"))
      (node (ref "C322") (pin "1") (pinfunction "1_1") (pintype "passive"))
      (node (ref "C330") (pin "2") (pinfunction "2_2") (pintype "passive"))
      (node (ref "D31") (pin "2") (pinfunction "K_2") (pintype "passive"))
      (node (ref "D32") (pin "2") (pinfunction "K_2") (pintype "passive"))
      (node (ref "D33") (pin "2") (pinfunction "K_2") (pintype "passive"))
      (node (ref "L37") (pin "2") (pinfunction "2_2") (pintype "passive"))
      (node (ref "U111") (pin "25") (pinfunction "VAA_25") (pintype "passive"))
      (node (ref "U112") (pin "2") (pinfunction "2_2") (pintype "passive"))
    )
    (net (code "60") (name "7393_VDD") (class "Default")
      (node (ref "C333") (pin "1") (pinfunction "1_1") (pintype "passive"))
      (node (ref "C334") (pin "2") (pinfunction "2_2") (pintype "passive"))
      (node (ref "C339") (pin "1") (pinfunction "1_1") (pintype "passive"))
      (node (ref "C340") (pin "2") (pinfunction "2_2") (pintype "passive"))
      (node (ref "L40") (pin "2") (pinfunction "2_2") (pintype "passive"))
      (node (ref "U111") (pin "35") (pinfunction "VDD_35") (pintype "passive"))
      (node (ref "U111") (pin "6") (pinfunction "VDD_6") (pintype "passive"))
    )
    (net (code "61") (name "7393_VDDIO") (class "Default")
      (node (ref "C335") (pin "1") (pinfunction "1_1") (pintype "passive"))
      (node (ref "C336") (pin "2") (pinfunction "2_2") (pintype "passive"))
      (node (ref "C346") (pin "1") (pinfunction "1_1") (pintype "passive"))
      (node (ref "C348") (pin "1") (pinfunction "1_1") (pintype "passive"))
      (node (ref "C350") (pin "1") (pinfunction "1_1") (pintype "passive"))
      (node (ref "D34") (pin "3") (pinfunction "C_3") (pintype "passive"))
      (node (ref "L41") (pin "2") (pinfunction "2_2") (pintype "passive"))
      (node (ref "R171") (pin "2") (pinfunction "2_2") (pintype "passive"))
      (node (ref "U111") (pin "1") (pinfunction "VDD_IO_1") (pintype "passive"))
      (node (ref "U115") (pin "23") (pinfunction "VCCB_23") (pintype "passive"))
      (node (ref "U115") (pin "24") (pinfunction "VCCB_24") (pintype "passive"))
      (node (ref "U116") (pin "23") (pinfunction "VCCB_23") (pintype "passive"))
      (node (ref "U116") (pin "24") (pinfunction "VCCB_24") (pintype "passive"))
      (node (ref "U117") (pin "23") (pinfunction "VCCB_23") (pintype "passive"))
      (node (ref "U117") (pin "24") (pinfunction "VCCB_24") (pintype "passive"))
    )
    (net (code "62") (name "GND") (class "Default")
      (node (ref "C314") (pin "1") (pinfunction "1_1") (pintype "passive"))
      (node (ref "C315") (pin "1") (pinfunction "1_1") (pintype "passive"))
      (node (ref "C319") (pin "2") (pinfunction "2_2") (pintype "passive"))
      (node (ref "C322") (pin "2") (pinfunction "2_2") (pintype "passive"))
      (node (ref "C328") (pin "1") (pinfunction "1_1") (pintype "passive"))
      (node (ref "C329") (pin "1") (pinfunction "1_1") (pintype "passive"))
      (node (ref "C330") (pin "1") (pinfunction "1_1") (pintype "passive"))
      (node (ref "C331") (pin "2") (pinfunction "2_2") (pintype "passive"))
      (node (ref "C332") (pin "1") (pinfunction "1_1") (pintype "passive"))
      (node (ref "C333") (pin "2") (pinfunction "2_2") (pintype "passive"))
      (node (ref "C334") (pin "1") (pinfunction "1_1") (pintype "passive"))
      (node (ref "C335") (pin "2") (pinfunction "2_2") (pintype "passive"))
      (node (ref "C336") (pin "1") (pinfunction "1_1") (pintype "passive"))
      (node (ref "C337") (pin "1") (pinfunction "1_1") (pintype "passive"))
      (node (ref "C338") (pin "1") (pinfunction "1_1") (pintype "passive"))
      (node (ref "C339") (pin "2") (pinfunction "2_2") (pintype "passive"))
      (node (ref "C340") (pin "1") (pinfunction "1_1") (pintype "passive"))
      (node (ref "C343") (pin "1") (pinfunction "1_1") (pintype "passive"))
      (node (ref "C344") (pin "1") (pinfunction "1_1") (pintype "passive"))
      (node (ref "C345") (pin "2") (pinfunction "2_2") (pintype "passive"))
      (node (ref "C346") (pin "2") (pinfunction "2_2") (pintype "passive"))
      (node (ref "C347") (pin "2") (pinfunction "2_2") (pintype "passive"))
      (node (ref "C348") (pin "2") (pinfunction "2_2") (pintype "passive"))
      (node (ref "C349") (pin "2") (pinfunction "2_2") (pintype "passive"))
      (node (ref "C350") (pin "2") (pinfunction "2_2") (pintype "passive"))
      (node (ref "D26") (pin "2") (pinfunction "2_2") (pintype "passive"))
      (node (ref "D30") (pin "2") (pinfunction "A_2") (pintype "passive"))
      (node (ref "D31") (pin "1") (pinfunction "A_1") (pintype "passive"))
      (node (ref "D32") (pin "1") (pinfunction "A_1") (pintype "passive"))
      (node (ref "D33") (pin "1") (pinfunction "A_1") (pintype "passive"))
      (node (ref "L36") (pin "2") (pinfunction "2_2") (pintype "passive"))
      (node (ref "R120") (pin "1") (pinfunction "1_1") (pintype "passive"))
      (node (ref "R120") (pin "2") (pinfunction "2_2") (pintype "passive"))
      (node (ref "R121") (pin "2") (pinfunction "2_2") (pintype "passive"))
      (node (ref "R158") (pin "1") (pinfunction "1_1") (pintype "passive"))
      (node (ref "R170") (pin "2") (pinfunction "2_2") (pintype "passive"))
      (node (ref "R172") (pin "2") (pinfunction "2_2") (pintype "passive"))
      (node (ref "R174") (pin "2") (pinfunction "2_2") (pintype "passive"))
      (node (ref "R175") (pin "1") (pinfunction "1_1") (pintype "passive"))
      (node (ref "R176") (pin "1") (pinfunction "1_1") (pintype "passive"))
      (node (ref "U104") (pin "29") (pinfunction "EP_29") (pintype "passive"))
      (node (ref "U104") (pin "3") (pinfunction "GND_3") (pintype "passive"))
      (node (ref "U105") (pin "2") (pinfunction "2_2") (pintype "passive"))
      (node (ref "U111") (pin "21") (pinfunction "PGND_21") (pintype "passive"))
      (node (ref "U111") (pin "24") (pinfunction "AGND_24") (pintype "passive"))
      (node (ref "U111") (pin "31") (pinfunction "SFL_31") (pintype "passive"))
      (node (ref "U111") (pin "36") (pinfunction "DGND_36") (pintype "passive"))
      (node (ref "U111") (pin "40") (pinfunction "GND_IO_40") (pintype "passive"))
      (node (ref "U111") (pin "41") (pinfunction "EP_41") (pintype "passive"))
      (node (ref "U111") (pin "7") (pinfunction "DGND_7") (pintype "passive"))
      (node (ref "U114") (pin "2") (pinfunction "GND_2") (pintype "passive"))
      (node (ref "U115") (pin "11") (pinfunction "GND_11") (pintype "passive"))
      (node (ref "U115") (pin "12") (pinfunction "GND_12") (pintype "passive"))
      (node (ref "U115") (pin "13") (pinfunction "GND_13") (pintype "passive"))
      (node (ref "U115") (pin "22") (pinfunction "OE#_22") (pintype "passive"))
      (node (ref "U116") (pin "11") (pinfunction "GND_11") (pintype "passive"))
      (node (ref "U116") (pin "12") (pinfunction "GND_12") (pintype "passive"))
      (node (ref "U116") (pin "13") (pinfunction "GND_13") (pintype "passive"))
      (node (ref "U116") (pin "22") (pinfunction "OE#_22") (pintype "passive"))
      (node (ref "U117") (pin "11") (pinfunction "GND_11") (pintype "passive"))
      (node (ref "U117") (pin "12") (pinfunction "GND_12") (pintype "passive"))
      (node (ref "U117") (pin "13") (pinfunction "GND_13") (pintype "passive"))
      (node (ref "U117") (pin "22") (pinfunction "OE#_22") (pintype "passive"))
      (node (ref "U118") (pin "2") (pinfunction "2_2") (pintype "passive"))
      (node (ref "U118") (pin "3") (pinfunction "3_3") (pintype "passive"))
      (node (ref "U120") (pin "1") (pinfunction "1_1") (pintype "passive"))
      (node (ref "U120") (pin "2") (pinfunction "2_2") (pintype "passive"))
      (node (ref "U120") (pin "5") (pinfunction "5_5") (pintype "passive"))
      (node (ref "U120") (pin "6") (pinfunction "6_6") (pintype "passive"))
      (node (ref "U120") (pin "7") (pinfunction "7_7") (pintype "passive"))
      (node (ref "USB4") (pin "1") (pinfunction "GND_1") (pintype "passive"))
      (node (ref "USB4") (pin "12") (pinfunction "GND_12") (pintype "passive"))
      (node (ref "USB4") (pin "4") (pinfunction "CC1_4") (pintype "passive"))
    )
    (net (code "63") (name "Net-(C342-Pad1)") (class "Default")
      (node (ref "C342") (pin "1") (pinfunction "1_1") (pintype "passive"))
      (node (ref "R173") (pin "2") (pinfunction "2_2") (pintype "passive"))
    )
    (net (code "64") (name "Net-(D29-A)") (class "Default")
      (node (ref "D29") (pin "2") (pinfunction "A_2") (pintype "passive"))
      (node (ref "F3") (pin "1") (pinfunction "1_1") (pintype "passive"))
    )
    (net (code "65") (name "Net-(D34-A-Pad1)") (class "Default")
      (node (ref "D34") (pin "1") (pinfunction "A_1") (pintype "passive"))
      (node (ref "R182") (pin "1") (pinfunction "1_1") (pintype "passive"))
    )
    (net (code "66") (name "Net-(D34-A-Pad2)") (class "Default")
      (node (ref "D34") (pin "2") (pinfunction "A_2") (pintype "passive"))
      (node (ref "R183") (pin "2") (pinfunction "2_2") (pintype "passive"))
    )
    (net (code "67") (name "Net-(L36-Pad1)") (class "Default")
      (node (ref "L36") (pin "1") (pinfunction "1_1") (pintype "passive"))
      (node (ref "USB4") (pin "13") (pinfunction "SHELL_13") (pintype "passive"))
      (node (ref "USB4") (pin "14") (pinfunction "SHELL_14") (pintype "passive"))
    )
    (net (code "68") (name "Net-(U104-RSTb)") (class "Default")
      (node (ref "R31") (pin "2") (pinfunction "2_2") (pintype "passive"))
      (node (ref "U104") (pin "9") (pinfunction "RSTb_9") (pintype "passive"))
    )
    (net (code "69") (name "Net-(U104-SUSPENDb)") (class "Default")
      (node (ref "U104") (pin "11") (pinfunction "SUSPENDb_11") (pintype "passive"))
      (node (ref "U105") (pin "1") (pinfunction "1_1") (pintype "passive"))
    )
    (net (code "70") (name "Net-(U104-VBUS)") (class "Default")
      (node (ref "R157") (pin "1") (pinfunction "1_1") (pintype "passive"))
      (node (ref "R158") (pin "2") (pinfunction "2_2") (pintype "passive"))
      (node (ref "U104") (pin "8") (pinfunction "VBUS_8") (pintype "passive"))
    )
    (net (code "71") (name "Net-(U108-A)") (class "Default")
      (node (ref "R164") (pin "1") (pinfunction "1_1") (pintype "passive"))
      (node (ref "U108") (pin "2") (pinfunction "A_2") (pintype "passive"))
    )
    (net (code "72") (name "Net-(U109-A)") (class "Default")
      (node (ref "R165") (pin "1") (pinfunction "1_1") (pintype "passive"))
      (node (ref "U109") (pin "2") (pinfunction "A_2") (pintype "passive"))
    )
    (net (code "73") (name "Net-(U111-EXT_LF)") (class "Default")
      (node (ref "C341") (pin "1") (pinfunction "1_1") (pintype "passive"))
      (node (ref "R173") (pin "1") (pinfunction "1_1") (pintype "passive"))
      (node (ref "U111") (pin "22") (pinfunction "EXT_LF_22") (pintype "passive"))
    )
    (net (code "74") (name "Net-(USB4-CC2)") (class "Default")
      (node (ref "R121") (pin "1") (pinfunction "1_1") (pintype "passive"))
      (node (ref "USB4") (pin "10") (pinfunction "CC2_10") (pintype "passive"))
    )
    (net (code "75") (name "Net-(USB4-DN1)") (class "Default")
      (node (ref "L35") (pin "2") (pinfunction "2_2") (pintype "passive"))
      (node (ref "USB4") (pin "5") (pinfunction "DN2_5") (pintype "passive"))
      (node (ref "USB4") (pin "7") (pinfunction "DN1_7") (pintype "passive"))
    )
    (net (code "76") (name "Net-(USB4-DP1)") (class "Default")
      (node (ref "L35") (pin "1") (pinfunction "1_1") (pintype "passive"))
      (node (ref "USB4") (pin "6") (pinfunction "DP1_6") (pintype "passive"))
      (node (ref "USB4") (pin "8") (pinfunction "DP2_8") (pintype "passive"))
    )
    (net (code "77") (name "USB_5V") (class "Default")
      (node (ref "D26") (pin "1") (pinfunction "1_1") (pintype "passive"))
      (node (ref "D30") (pin "1") (pinfunction "C_1") (pintype "passive"))
      (node (ref "F3") (pin "2") (pinfunction "2_2") (pintype "passive"))
      (node (ref "R157") (pin "2") (pinfunction "2_2") (pintype "passive"))
      (node (ref "USB4") (pin "11") (pinfunction "VBUS_11") (pintype "passive"))
      (node (ref "USB4") (pin "2") (pinfunction "VBUS_2") (pintype "passive"))
    )
    (net (code "78") (name "VCC_1V5") (class "Default")
      (node (ref "C345") (pin "1") (pinfunction "1_1") (pintype "passive"))
      (node (ref "C347") (pin "1") (pinfunction "1_1") (pintype "passive"))
      (node (ref "C349") (pin "1") (pinfunction "1_1") (pintype "passive"))
      (node (ref "Q17") (pin "1") (pinfunction "G_1") (pintype "passive"))
      (node (ref "Q18") (pin "1") (pinfunction "G_1") (pintype "passive"))
      (node (ref "R180") (pin "2") (pinfunction "2_2") (pintype "passive"))
      (node (ref "R181") (pin "2") (pinfunction "2_2") (pintype "passive"))
      (node (ref "U115") (pin "1") (pinfunction "VCCA_1") (pintype "passive"))
      (node (ref "U115") (pin "2") (pinfunction "DIR_2") (pintype "passive"))
      (node (ref "U116") (pin "1") (pinfunction "VCCA_1") (pintype "passive"))
      (node (ref "U116") (pin "2") (pinfunction "DIR_2") (pintype "passive"))
      (node (ref "U117") (pin "1") (pinfunction "VCCA_1") (pintype "passive"))
      (node (ref "U117") (pin "2") (pinfunction "DIR_2") (pintype "passive"))
    )
    (net (code "79") (name "VCC_1V8") (class "Default")
      (node (ref "C337") (pin "2") (pinfunction "2_2") (pintype "passive"))
      (node (ref "C343") (pin "2") (pinfunction "2_2") (pintype "passive"))
      (node (ref "L42") (pin "1") (pinfunction "1_1") (pintype "passive"))
      (node (ref "U114") (pin "5") (pinfunction "OUT_5") (pintype "passive"))
    )
    (net (code "80") (name "VCC_3V3") (class "Default")
      (node (ref "C314") (pin "2") (pinfunction "2_2") (pintype "passive"))
      (node (ref "C315") (pin "2") (pinfunction "2_2") (pintype "passive"))
      (node (ref "C328") (pin "2") (pinfunction "2_2") (pintype "passive"))
      (node (ref "C344") (pin "2") (pinfunction "2_2") (pintype "passive"))
      (node (ref "L39") (pin "1") (pinfunction "1_1") (pintype "passive"))
      (node (ref "R164") (pin "2") (pinfunction "2_2") (pintype "passive"))
      (node (ref "R165") (pin "2") (pinfunction "2_2") (pintype "passive"))
      (node (ref "R31") (pin "1") (pinfunction "1_1") (pintype "passive"))
      (node (ref "U104") (pin "6") (pinfunction "VDD_6") (pintype "passive"))
      (node (ref "U104") (pin "7") (pinfunction "VREGIN_7") (pintype "passive"))
      (node (ref "U114") (pin "1") (pinfunction "IN_1") (pintype "passive"))
      (node (ref "U114") (pin "3") (pinfunction "EN_3") (pintype "passive"))
    )
    (net (code "81") (name "VCC_5V") (class "Default")
      (node (ref "D29") (pin "1") (pinfunction "K_1") (pintype "passive"))
    )
    (net (code "82") (name "unconnected-(U104-CHR0-Pad15)") (class "Default")
      (node (ref "U104") (pin "15") (pinfunction "CHR0_15") (pintype "passive+no_connect"))
    )
    (net (code "83") (name "unconnected-(U104-CHR1-Pad14)") (class "Default")
      (node (ref "U104") (pin "14") (pinfunction "CHR1_14") (pintype "passive+no_connect"))
    )
    (net (code "84") (name "unconnected-(U104-CHREN-Pad13)") (class "Default")
      (node (ref "U104") (pin "13") (pinfunction "CHREN_13") (pintype "passive+no_connect"))
    )
    (net (code "85") (name "unconnected-(U104-CTS-Pad23)") (class "Default")
      (node (ref "U104") (pin "23") (pinfunction "CTS_23") (pintype "passive+no_connect"))
    )
    (net (code "86") (name "unconnected-(U104-DCD-Pad1)") (class "Default")
      (node (ref "U104") (pin "1") (pinfunction "DCD_1") (pintype "passive+no_connect"))
    )
    (net (code "87") (name "unconnected-(U104-DSR-Pad27)") (class "Default")
      (node (ref "U104") (pin "27") (pinfunction "DSR_27") (pintype "passive+no_connect"))
    )
    (net (code "88") (name "unconnected-(U104-DTR-Pad28)") (class "Default")
      (node (ref "U104") (pin "28") (pinfunction "DTR_28") (pintype "passive+no_connect"))
    )
    (net (code "89") (name "unconnected-(U104-GPIO.0{slash}TXT-Pad19)") (class "Default")
      (node (ref "U104") (pin "19") (pinfunction "GPIO.0/TXT_19") (pintype "passive+no_connect"))
    )
    (net (code "90") (name "unconnected-(U104-GPIO.1{slash}RXT-Pad18)") (class "Default")
      (node (ref "U104") (pin "18") (pinfunction "GPIO.1/RXT_18") (pintype "passive+no_connect"))
    )
    (net (code "91") (name "unconnected-(U104-GPIO.2{slash}RS485-Pad17)") (class "Default")
      (node (ref "U104") (pin "17") (pinfunction "GPIO.2/RS485_17") (pintype "passive+no_connect"))
    )
    (net (code "92") (name "unconnected-(U104-GPIO.3{slash}WAKEUP-Pad16)") (class "Default")
      (node (ref "U104") (pin "16") (pinfunction "GPIO.3/WAKEUP_16") (pintype "passive+no_connect"))
    )
    (net (code "93") (name "unconnected-(U104-GPIO.4-Pad22)") (class "Default")
      (node (ref "U104") (pin "22") (pinfunction "GPIO.4_22") (pintype "passive+no_connect"))
    )
    (net (code "94") (name "unconnected-(U104-GPIO.5-Pad21)") (class "Default")
      (node (ref "U104") (pin "21") (pinfunction "GPIO.5_21") (pintype "passive+no_connect"))
    )
    (net (code "95") (name "unconnected-(U104-GPIO.6-Pad20)") (class "Default")
      (node (ref "U104") (pin "20") (pinfunction "GPIO.6_20") (pintype "passive+no_connect"))
    )
    (net (code "96") (name "unconnected-(U104-NC-Pad10)") (class "Default")
      (node (ref "U104") (pin "10") (pinfunction "NC_10") (pintype "passive+no_connect"))
    )
    (net (code "97") (name "unconnected-(U104-RI{slash}CLK-Pad2)") (class "Default")
      (node (ref "U104") (pin "2") (pinfunction "RI/CLK_2") (pintype "passive+no_connect"))
    )
    (net (code "98") (name "unconnected-(U104-RTS-Pad24)") (class "Default")
      (node (ref "U104") (pin "24") (pinfunction "RTS_24") (pintype "passive+no_connect"))
    )
    (net (code "99") (name "unconnected-(U104-SUSPEND-Pad12)") (class "Default")
      (node (ref "U104") (pin "12") (pinfunction "SUSPEND_12") (pintype "passive+no_connect"))
    )
    (net (code "100") (name "unconnected-(U114-N{slash}C-Pad4)") (class "Default")
      (node (ref "U114") (pin "4") (pinfunction "N/C_4") (pintype "passive+no_connect"))
    )
    (net (code "101") (name "unconnected-(U116-A7-Pad9)") (class "Default")
      (node (ref "U116") (pin "9") (pinfunction "A7_9") (pintype "passive+no_connect"))
    )
    (net (code "102") (name "unconnected-(U116-A8-Pad10)") (class "Default")
      (node (ref "U116") (pin "10") (pinfunction "A8_10") (pintype "passive+no_connect"))
    )
    (net (code "103") (name "unconnected-(U116-B7-Pad15)") (class "Default")
      (node (ref "U116") (pin "15") (pinfunction "B7_15") (pintype "passive+no_connect"))
    )
    (net (code "104") (name "unconnected-(U116-B8-Pad14)") (class "Default")
      (node (ref "U116") (pin "14") (pinfunction "B8_14") (pintype "passive+no_connect"))
    )
    (net (code "105") (name "unconnected-(U117-A1-Pad3)") (class "Default")
      (node (ref "U117") (pin "3") (pinfunction "A1_3") (pintype "passive+no_connect"))
    )
    (net (code "106") (name "unconnected-(U117-A2-Pad4)") (class "Default")
      (node (ref "U117") (pin "4") (pinfunction "A2_4") (pintype "passive+no_connect"))
    )
    (net (code "107") (name "unconnected-(U117-B1-Pad21)") (class "Default")
      (node (ref "U117") (pin "21") (pinfunction "B1_21") (pintype "passive+no_connect"))
    )
    (net (code "108") (name "unconnected-(U117-B2-Pad20)") (class "Default")
      (node (ref "U117") (pin "20") (pinfunction "B2_20") (pintype "passive+no_connect"))
    )
    (net (code "109") (name "unconnected-(USB4-SBU1-Pad9)") (class "Default")
      (node (ref "USB4") (pin "9") (pinfunction "SBU1_9") (pintype "passive+no_connect"))
    )
    (net (code "110") (name "unconnected-(USB4-SBU2-Pad3)") (class "Default")
      (node (ref "USB4") (pin "3") (pinfunction "SBU2_3") (pintype "passive+no_connect"))
    )
  )
)
